# RFID_Antenna.net
KiCad netlist of a schematic drawn in EAGLE
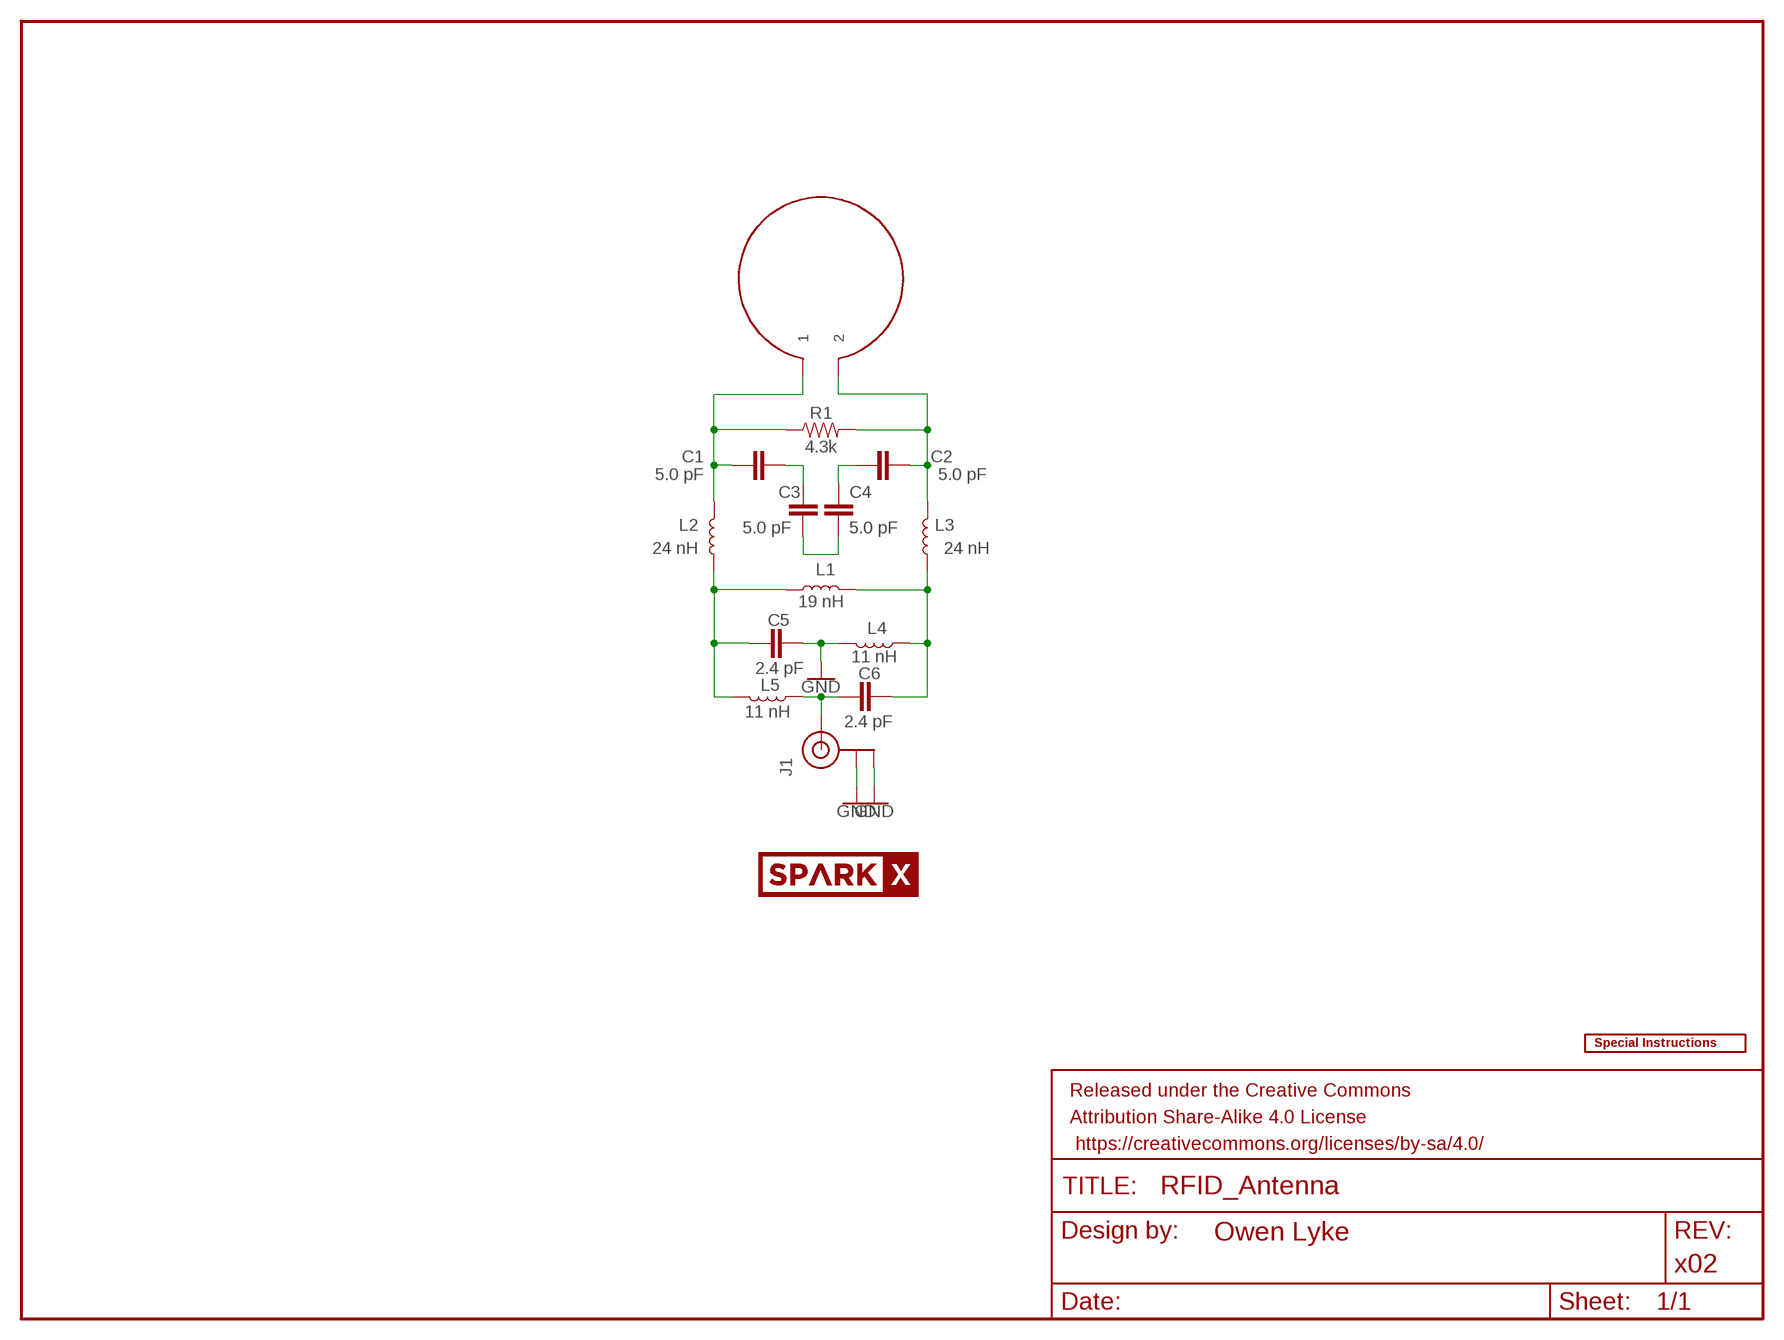
[diagram p0: schematic, sheet 1]

(export (version "E")
  (design (tool "Eeschema 10.0.6"))
  (components
    (comp (ref "C1")
      (value "5.0 pF")
      (footprint "eagle-import:0402_MURATA")
      (libsource (lib "eagle-import") (part "5.0PF-0402"))
    )
    (comp (ref "C2")
      (value "5.0 pF")
      (footprint "eagle-import:0402_MURATA")
      (libsource (lib "eagle-import") (part "5.0PF-0402"))
    )
    (comp (ref "C3")
      (value "5.0 pF")
      (footprint "eagle-import:0402_MURATA")
      (libsource (lib "eagle-import") (part "5.0PF-0402"))
    )
    (comp (ref "C4")
      (value "5.0 pF")
      (footprint "eagle-import:0402_MURATA")
      (libsource (lib "eagle-import") (part "5.0PF-0402"))
    )
    (comp (ref "C5")
      (value "2.4 pF")
      (footprint "eagle-import:0402_MURATA")
      (libsource (lib "eagle-import") (part "2.4PF-0402"))
    )
    (comp (ref "C6")
      (value "2.4 pF")
      (footprint "eagle-import:0402_MURATA")
      (libsource (lib "eagle-import") (part "2.4PF-0402"))
    )
    (comp (ref "FRAME1")
      (value "FRAME-LETTER")
      (footprint "eagle-import:CREATIVE_COMMONS")
      (fields (field (name "DESIGNER") "Owen Lyke") (field (name "REV") "x02"))
      (libsource (lib "eagle-import") (part "FRAME-LETTER"))
    )
    (comp (ref "J1")
      (value "U.FL")
      (footprint "eagle-import:U.FL")
      (libsource (lib "eagle-import") (part "U.FL"))
    )
    (comp (ref "L1")
      (value "19 nH")
      (footprint "eagle-import:0402_MURATA")
      (libsource (lib "eagle-import") (part "19NH-0402"))
    )
    (comp (ref "L2")
      (value "24 nH")
      (footprint "eagle-import:0603_MURATA")
      (libsource (lib "eagle-import") (part "24NH-0603"))
    )
    (comp (ref "L3")
      (value "24 nH")
      (footprint "eagle-import:0603_MURATA")
      (libsource (lib "eagle-import") (part "24NH-0603"))
    )
    (comp (ref "L4")
      (value "11 nH")
      (footprint "eagle-import:0603_MURATA")
      (libsource (lib "eagle-import") (part "11NH-0603"))
    )
    (comp (ref "L5")
      (value "11 nH")
      (footprint "eagle-import:0603_MURATA")
      (libsource (lib "eagle-import") (part "11NH-0603"))
    )
    (comp (ref "R1")
      (value "4.3k")
      (footprint "eagle-import:0402_MURATA")
      (libsource (lib "eagle-import") (part "4.3KOHM-0402"))
    )
    (comp (ref "U$1")
      (value "ANTENNA")
      (footprint "eagle-import:ANT")
      (libsource (lib "eagle-import") (part "ANTENNA"))
    )
    (comp (ref "U$2")
      (value "SPECIAL_INSTRUCTIONS-ORDERING")
      (footprint "eagle-import:ORDERING_INSTRUCTIONS")
      (libsource (lib "eagle-import") (part "SPECIAL_INSTRUCTIONS-ORDERING"))
    )
    (comp (ref "U$12")
      (value "SPARKX-LOGO6")
      (footprint "eagle-import:SPARKX-XLARGE")
      (libsource (lib "eagle-import") (part "SPARKX-LOGO6"))
    )
  )
  (nets
    (net (code "1") (name "GND") (class "Default")
      (node (ref "C5") (pin "P$1") (pinfunction "1_P$1") (pintype "passive"))
      (node (ref "J1") (pin "1") (pinfunction "GND_1") (pintype "bidirectional"))
      (node (ref "J1") (pin "2") (pinfunction "GND_2") (pintype "bidirectional"))
      (node (ref "L4") (pin "P$2") (pinfunction "2_P$2") (pintype "passive"))
    )
    (net (code "2") (name "Net-(C1-1)") (class "Default")
      (node (ref "C1") (pin "P$1") (pinfunction "1_P$1") (pintype "passive"))
      (node (ref "L2") (pin "P$2") (pinfunction "2_P$2") (pintype "passive"))
      (node (ref "R1") (pin "P$1") (pinfunction "1_P$1") (pintype "passive"))
      (node (ref "U$1") (pin "P$1") (pinfunction "1_P$1") (pintype "bidirectional"))
      (node (ref "U$1") (pin "P$3") (pinfunction "1_P$3") (pintype "bidirectional"))
    )
    (net (code "3") (name "Net-(C1-2)") (class "Default")
      (node (ref "C1") (pin "P$2") (pinfunction "2_P$2") (pintype "passive"))
      (node (ref "C3") (pin "P$1") (pinfunction "1_P$1") (pintype "passive"))
    )
    (net (code "4") (name "Net-(C2-1)") (class "Default")
      (node (ref "C2") (pin "P$1") (pinfunction "1_P$1") (pintype "passive"))
      (node (ref "C4") (pin "P$1") (pinfunction "1_P$1") (pintype "passive"))
    )
    (net (code "5") (name "Net-(C2-2)") (class "Default")
      (node (ref "C2") (pin "P$2") (pinfunction "2_P$2") (pintype "passive"))
      (node (ref "L3") (pin "P$2") (pinfunction "2_P$2") (pintype "passive"))
      (node (ref "R1") (pin "P$2") (pinfunction "2_P$2") (pintype "passive"))
      (node (ref "U$1") (pin "P$2") (pinfunction "2_P$2") (pintype "bidirectional"))
      (node (ref "U$1") (pin "P$4") (pinfunction "2_P$4") (pintype "bidirectional"))
    )
    (net (code "6") (name "Net-(C3-2)") (class "Default")
      (node (ref "C3") (pin "P$2") (pinfunction "2_P$2") (pintype "passive"))
      (node (ref "C4") (pin "P$2") (pinfunction "2_P$2") (pintype "passive"))
    )
    (net (code "7") (name "Net-(C5-2)") (class "Default")
      (node (ref "C5") (pin "P$2") (pinfunction "2_P$2") (pintype "passive"))
      (node (ref "L1") (pin "P$1") (pinfunction "1_P$1") (pintype "passive"))
      (node (ref "L2") (pin "P$1") (pinfunction "1_P$1") (pintype "passive"))
      (node (ref "L5") (pin "P$2") (pinfunction "2_P$2") (pintype "passive"))
    )
    (net (code "8") (name "Net-(C6-1)") (class "Default")
      (node (ref "C6") (pin "P$1") (pinfunction "1_P$1") (pintype "passive"))
      (node (ref "L1") (pin "P$2") (pinfunction "2_P$2") (pintype "passive"))
      (node (ref "L3") (pin "P$1") (pinfunction "1_P$1") (pintype "passive"))
      (node (ref "L4") (pin "P$1") (pinfunction "1_P$1") (pintype "passive"))
    )
    (net (code "9") (name "Net-(C6-2)") (class "Default")
      (node (ref "C6") (pin "P$2") (pinfunction "2_P$2") (pintype "passive"))
      (node (ref "J1") (pin "FEED") (pinfunction "SIGNAL_FEED") (pintype "bidirectional"))
      (node (ref "L5") (pin "P$1") (pinfunction "1_P$1") (pintype "passive"))
    )
  )
)
